# XRONOS_CLOCK_V2_1.net
KiCad netlist of a schematic drawn in EAGLE
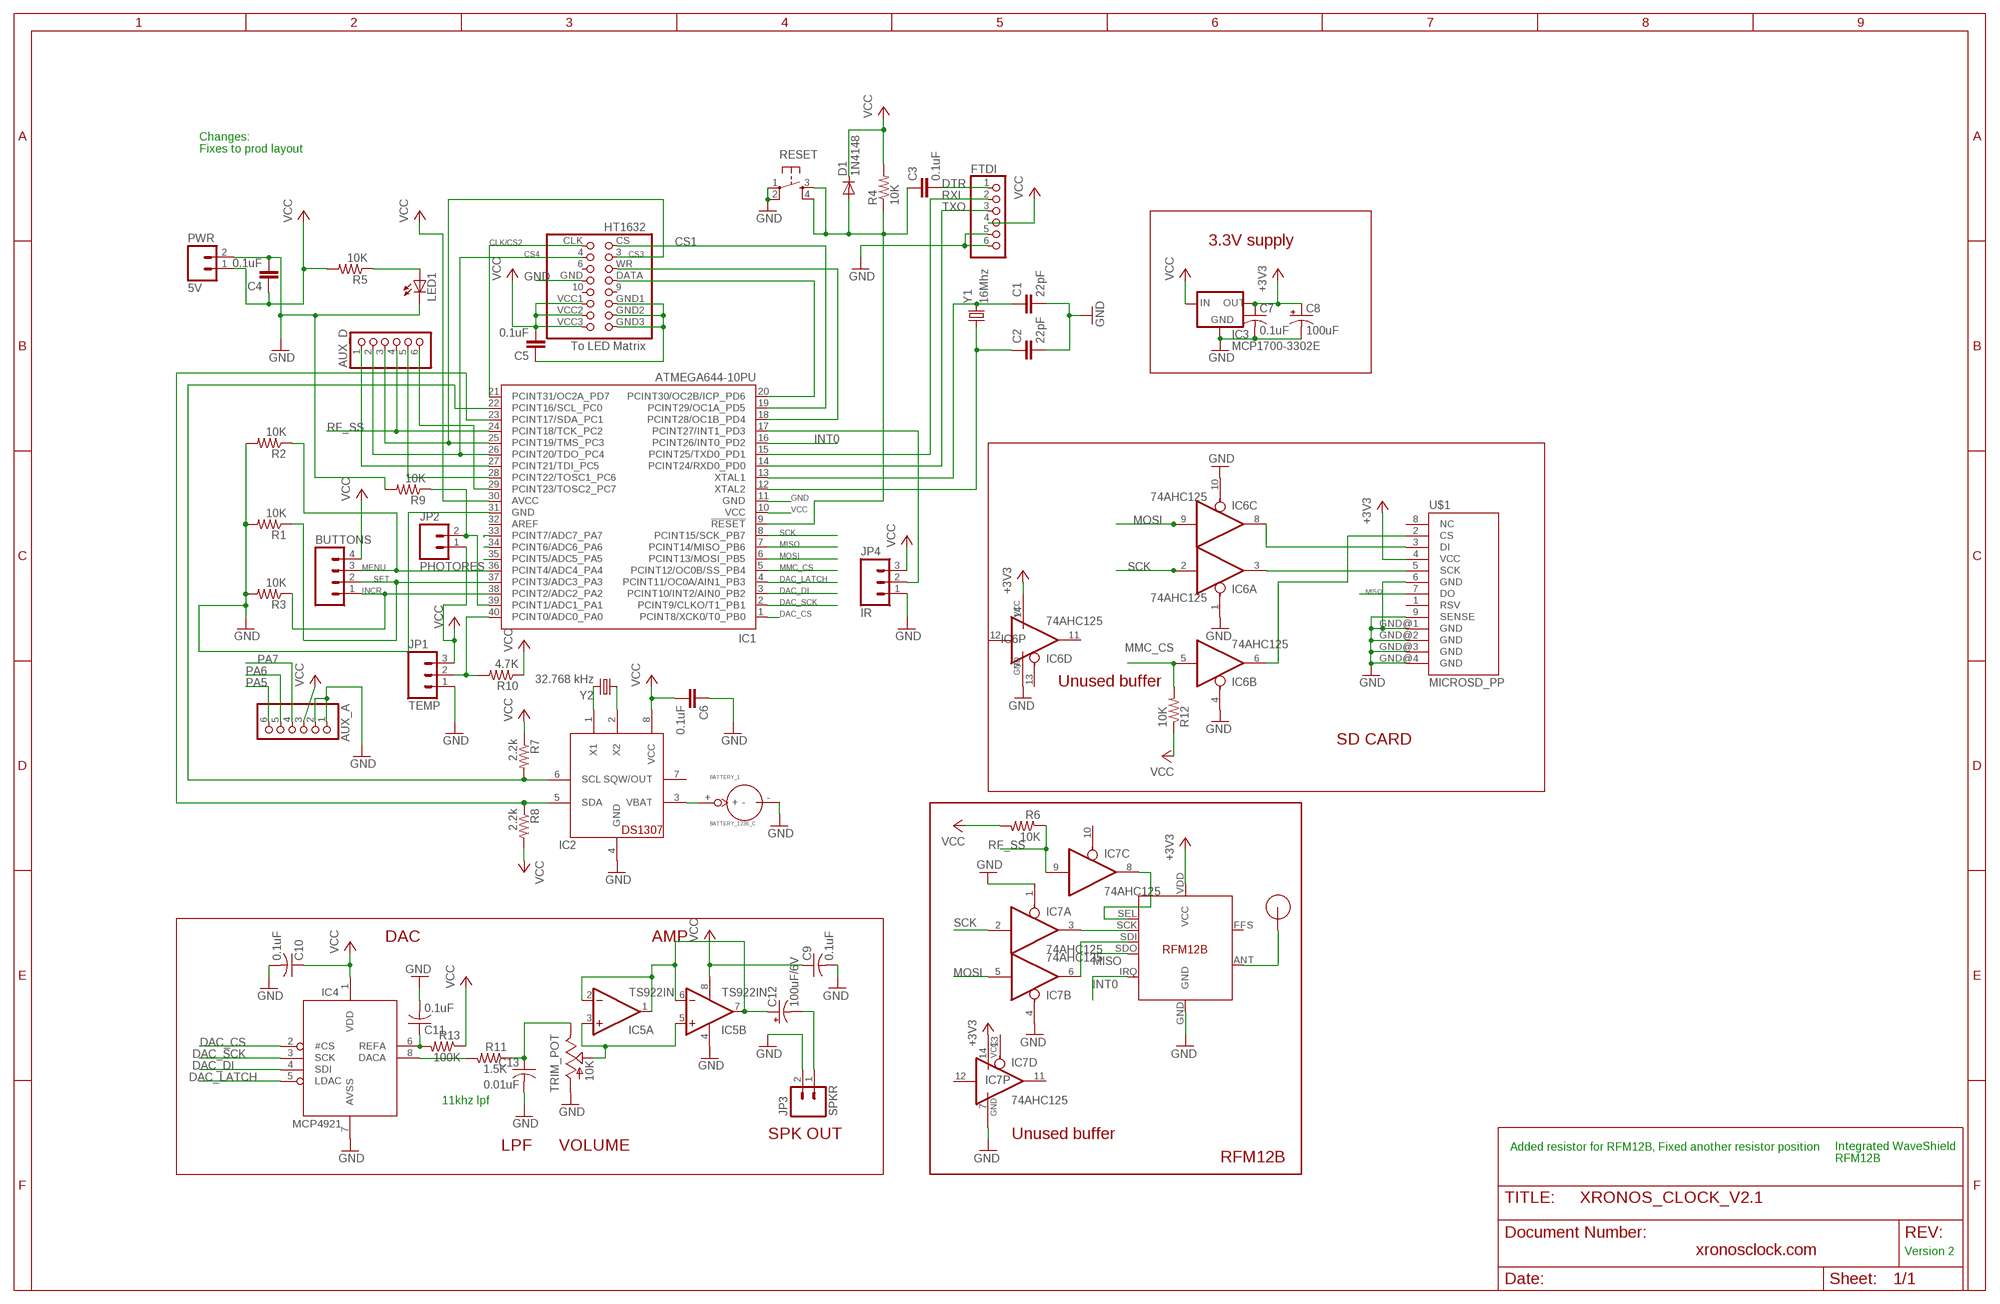
[diagram p0: schematic, sheet 1]

(export (version "E")
  (design (tool "Eeschema 10.0.6"))
  (components
    (comp (ref "AUX_A")
      (value "PINHD-1X6")
      (footprint "eagle-import:1X06")
      (libsource (lib "eagle-import") (part "PINHD-1X6"))
    )
    (comp (ref "AUX_D")
      (value "PINHD-1X6")
      (footprint "eagle-import:1X06")
      (libsource (lib "eagle-import") (part "PINHD-1X6"))
    )
    (comp (ref "BATTERY_1")
      (value "BATTERY_1236_C")
      (footprint "eagle-import:BATTERY_1236_C")
      (libsource (lib "eagle-import") (part "BATTERY_1236_C"))
    )
    (comp (ref "BUTTONS")
      (value "M04POLAR")
      (footprint "eagle-import:MOLEX-1X4")
      (libsource (lib "eagle-import") (part "M04POLAR"))
    )
    (comp (ref "C1")
      (value "22pF")
      (footprint "eagle-import:C025-024X044")
      (libsource (lib "eagle-import") (part "C-EU025-024X044"))
    )
    (comp (ref "C2")
      (value "22pF")
      (footprint "eagle-import:C025-024X044")
      (libsource (lib "eagle-import") (part "C-EU025-024X044"))
    )
    (comp (ref "C3")
      (value "0.1uF")
      (footprint "eagle-import:C025-024X044")
      (libsource (lib "eagle-import") (part "C-EU025-024X044"))
    )
    (comp (ref "C4")
      (value "0.1uF")
      (footprint "eagle-import:C025-024X044")
      (libsource (lib "eagle-import") (part "C-EU025-024X044"))
    )
    (comp (ref "C5")
      (value "0.1uF")
      (footprint "eagle-import:C025-024X044")
      (libsource (lib "eagle-import") (part "C-EU025-024X044"))
    )
    (comp (ref "C6")
      (value "0.1uF")
      (footprint "eagle-import:C025-024X044")
      (libsource (lib "eagle-import") (part "C-EU025-024X044"))
    )
    (comp (ref "C7")
      (value "0.1uF")
      (footprint "eagle-import:C025-025X050")
      (libsource (lib "eagle-import") (part "C-US025-025X050"))
    )
    (comp (ref "C8")
      (value "100uF")
      (footprint "eagle-import:E2,5-5")
      (libsource (lib "eagle-import") (part "CPOL-USE2.5-5"))
    )
    (comp (ref "C9")
      (value "0.1uF")
      (footprint "eagle-import:C025-025X050")
      (libsource (lib "eagle-import") (part "C-US025-025X050"))
    )
    (comp (ref "C10")
      (value "0.1uF")
      (footprint "eagle-import:C025-025X050")
      (libsource (lib "eagle-import") (part "C-US025-025X050"))
    )
    (comp (ref "C11")
      (value "0.1uF")
      (footprint "eagle-import:C025-025X050")
      (libsource (lib "eagle-import") (part "C-US025-025X050"))
    )
    (comp (ref "C12")
      (value "100uF/6V")
      (footprint "eagle-import:E2,5-5")
      (libsource (lib "eagle-import") (part "CPOL-USE2.5-5"))
    )
    (comp (ref "C13")
      (value "0.01uF")
      (footprint "eagle-import:C025-025X050")
      (libsource (lib "eagle-import") (part "C-US025-025X050"))
    )
    (comp (ref "D1")
      (value "1N4148")
      (footprint "eagle-import:DO35-7")
      (libsource (lib "eagle-import") (part "1N4148DO35-7"))
    )
    (comp (ref "FTDI")
      (value "PINHD-1X6")
      (footprint "eagle-import:1X06")
      (libsource (lib "eagle-import") (part "PINHD-1X6"))
    )
    (comp (ref "HT1632")
      (value "To LED Matrix")
      (footprint "eagle-import:IDC2X08")
      (libsource (lib "eagle-import") (part "HT1632"))
    )
    (comp (ref "IC1")
      (value "ATMEGA644-10PU")
      (footprint "eagle-import:DIL40")
      (fields (field (name "MPN") "ATMEGA644V-10PU"))
      (libsource (lib "eagle-import") (part "ATMEGA644-PU10"))
    )
    (comp (ref "IC2")
      (value "DS1307")
      (footprint "eagle-import:DIL08")
      (libsource (lib "eagle-import") (part "DS1307"))
    )
    (comp (ref "IC3")
      (value "MCP1700-3302E")
      (footprint "eagle-import:TO92")
      (libsource (lib "eagle-import") (part "MCP1700TRI"))
    )
    (comp (ref "IC4")
      (value "MCP4921")
      (footprint "eagle-import:DIL08")
      (libsource (lib "eagle-import") (part "MCP4921"))
    )
    (comp (ref "IC5")
      (value "TS922IN")
      (footprint "eagle-import:DIL08")
      (libsource (lib "eagle-import") (part "TL072P"))
    )
    (comp (ref "IC6")
      (value "74AHC125")
      (footprint "eagle-import:DIL14-LARDO")
      (libsource (lib "eagle-import") (part "74125N-LARDO"))
    )
    (comp (ref "IC7")
      (value "74AHC125")
      (footprint "eagle-import:DIL14")
      (libsource (lib "eagle-import") (part "74125N"))
    )
    (comp (ref "JP1")
      (value "TEMP")
      (footprint "eagle-import:MOLEX-1X3")
      (libsource (lib "eagle-import") (part "M03POLAR"))
    )
    (comp (ref "JP2")
      (value "PHOTORES")
      (footprint "eagle-import:MOLEX-1X2")
      (libsource (lib "eagle-import") (part "M02POLAR"))
    )
    (comp (ref "JP3")
      (value "SPKR")
      (footprint "eagle-import:MOLEX-1X2")
      (libsource (lib "eagle-import") (part "M02POLAR"))
    )
    (comp (ref "JP4")
      (value "IR")
      (footprint "eagle-import:MOLEX-1X3_LOCK")
      (libsource (lib "eagle-import") (part "M03POLAR_LOCK"))
    )
    (comp (ref "LED1")
      (value "LED-3MM-NO_SILK")
      (footprint "eagle-import:LED3MM-NS")
      (libsource (lib "eagle-import") (part "LED-3MM-NO_SILK"))
    )
    (comp (ref "PWR")
      (value "5V")
      (footprint "eagle-import:MOLEX-1X2")
      (libsource (lib "eagle-import") (part "M02POLAR"))
    )
    (comp (ref "R1")
      (value "10K")
      (footprint "eagle-import:AXIAL-0.3EZ")
      (libsource (lib "eagle-import") (part "RESISTOREZ"))
    )
    (comp (ref "R2")
      (value "10K")
      (footprint "eagle-import:AXIAL-0.3EZ")
      (libsource (lib "eagle-import") (part "RESISTOREZ"))
    )
    (comp (ref "R3")
      (value "10K")
      (footprint "eagle-import:AXIAL-0.3EZ")
      (libsource (lib "eagle-import") (part "RESISTOREZ"))
    )
    (comp (ref "R4")
      (value "10K")
      (footprint "eagle-import:AXIAL-0.3EZ")
      (libsource (lib "eagle-import") (part "RESISTOREZ"))
    )
    (comp (ref "R5")
      (value "10K")
      (footprint "eagle-import:AXIAL-0.3EZ")
      (libsource (lib "eagle-import") (part "RESISTOREZ"))
    )
    (comp (ref "R6")
      (value "10K")
      (footprint "eagle-import:AXIAL-0.3")
      (libsource (lib "eagle-import") (part "RESISTORAXIAL-0.3"))
    )
    (comp (ref "R7")
      (value "2.2k")
      (footprint "eagle-import:AXIAL-0.3EZ")
      (libsource (lib "eagle-import") (part "RESISTOREZ"))
    )
    (comp (ref "R8")
      (value "2.2k")
      (footprint "eagle-import:AXIAL-0.3EZ")
      (libsource (lib "eagle-import") (part "RESISTOREZ"))
    )
    (comp (ref "R9")
      (value "10K")
      (footprint "eagle-import:AXIAL-0.3EZ")
      (libsource (lib "eagle-import") (part "RESISTOREZ"))
    )
    (comp (ref "R10")
      (value "4.7K")
      (footprint "eagle-import:AXIAL-0.3EZ")
      (libsource (lib "eagle-import") (part "RESISTOREZ"))
    )
    (comp (ref "R11")
      (value "1.5K")
      (footprint "eagle-import:AXIAL-0.3")
      (libsource (lib "eagle-import") (part "RESISTORAXIAL-0.3"))
    )
    (comp (ref "R12")
      (value "10K")
      (footprint "eagle-import:AXIAL-0.3")
      (libsource (lib "eagle-import") (part "RESISTORAXIAL-0.3"))
    )
    (comp (ref "R13")
      (value "100K")
      (footprint "eagle-import:AXIAL-0.3")
      (libsource (lib "eagle-import") (part "RESISTORAXIAL-0.3"))
    )
    (comp (ref "RESET")
      (value "TAC_SWITCHPTH")
      (footprint "eagle-import:TACTILE-PTH")
      (libsource (lib "eagle-import") (part "TAC_SWITCHPTH"))
    )
    (comp (ref "TRIM_POT")
      (value "10K")
      (footprint "eagle-import:B25P")
      (libsource (lib "eagle-import") (part "TRIM_US-B25P"))
    )
    (comp (ref "U$1")
      (value "MICROSD_PP")
      (footprint "eagle-import:MICROSD_PP")
      (libsource (lib "eagle-import") (part "MICROSD_PP"))
    )
    (comp (ref "U$2")
      (value "RFM12B")
      (footprint "eagle-import:RFM12B")
      (libsource (lib "eagle-import") (part "RFM12B"))
    )
    (comp (ref "U$3")
      (value "RFM12B_ANTENNA")
      (footprint "eagle-import:RFM12B-ANTENNA")
      (libsource (lib "eagle-import") (part "RFM12B_ANTENNA"))
    )
    (comp (ref "Y1")
      (value "16Mhz")
      (footprint "eagle-import:HC49US")
      (libsource (lib "eagle-import") (part "CRYSTALHC49US"))
    )
    (comp (ref "Y2")
      (value "32.768 kHz")
      (footprint "eagle-import:TC26HEZ")
      (libsource (lib "eagle-import") (part "CRYSTALTC26H_EZ"))
    )
  )
  (nets
    (net (code "1") (name "+3V3") (class "Default")
      (node (ref "C7") (pin "1") (pinfunction "1_1") (pintype "passive"))
      (node (ref "C8") (pin "+") (pinfunction "+_+") (pintype "passive"))
      (node (ref "IC3") (pin "3") (pinfunction "OUT_3") (pintype "passive"))
      (node (ref "IC6") (pin "14") (pinfunction "VCC_14") (pintype "power_in"))
      (node (ref "IC7") (pin "14") (pinfunction "VCC_14") (pintype "power_in"))
      (node (ref "U$1") (pin "4") (pinfunction "VCC_4") (pintype "bidirectional"))
      (node (ref "U$2") (pin "VDD") (pinfunction "VCC_VDD") (pintype "power_in"))
    )
    (net (code "2") (name "/CLK{slash}CS2") (class "Default")
      (node (ref "HT1632") (pin "CLK") (pinfunction "2_CLK") (pintype "passive"))
      (node (ref "IC1") (pin "21") (pinfunction "PCINT31/OC2A_PD7_21") (pintype "bidirectional"))
    )
    (net (code "3") (name "/CS1") (class "Default")
      (node (ref "HT1632") (pin "CS") (pinfunction "1_CS") (pintype "passive"))
      (node (ref "IC1") (pin "19") (pinfunction "PCINT29/OC1A_PD5_19") (pintype "bidirectional"))
    )
    (net (code "4") (name "/CS3") (class "Default")
      (node (ref "AUX_D") (pin "3") (pinfunction "3_3") (pintype "passive"))
      (node (ref "HT1632") (pin "3") (pinfunction "3_3") (pintype "passive"))
      (node (ref "IC1") (pin "25") (pinfunction "PCINT19/TMS_PC3_25") (pintype "bidirectional"))
    )
    (net (code "5") (name "/CS4") (class "Default")
      (node (ref "AUX_D") (pin "2") (pinfunction "2_2") (pintype "passive"))
      (node (ref "HT1632") (pin "4") (pinfunction "4_4") (pintype "passive"))
      (node (ref "IC1") (pin "26") (pinfunction "PCINT20/TDO_PC4_26") (pintype "bidirectional"))
    )
    (net (code "6") (name "/DAC_CS") (class "Default")
      (node (ref "IC1") (pin "1") (pinfunction "PCINT8/XCK0/T0_PB0_1") (pintype "bidirectional"))
      (node (ref "IC4") (pin "2") (pinfunction "#CS_2") (pintype "input"))
    )
    (net (code "7") (name "/DAC_DI") (class "Default")
      (node (ref "IC1") (pin "3") (pinfunction "PCINT10/INT2/AIN0_PB2_3") (pintype "bidirectional"))
      (node (ref "IC4") (pin "4") (pinfunction "SDI_4") (pintype "input"))
    )
    (net (code "8") (name "/DAC_LATCH") (class "Default")
      (node (ref "IC1") (pin "4") (pinfunction "PCINT11/OC0A/AIN1_PB3_4") (pintype "bidirectional"))
      (node (ref "IC4") (pin "5") (pinfunction "LDAC_5") (pintype "input"))
    )
    (net (code "9") (name "/DAC_SCK") (class "Default")
      (node (ref "IC1") (pin "2") (pinfunction "PCINT9/CLKO/T1_PB1_2") (pintype "bidirectional"))
      (node (ref "IC4") (pin "3") (pinfunction "SCK_3") (pintype "input"))
    )
    (net (code "10") (name "/DTR") (class "Default")
      (node (ref "C3") (pin "2") (pinfunction "2_2") (pintype "passive"))
      (node (ref "FTDI") (pin "1") (pinfunction "1_1") (pintype "passive"))
    )
    (net (code "11") (name "/INCR") (class "Default")
      (node (ref "BUTTONS") (pin "1") (pinfunction "1_1") (pintype "passive"))
      (node (ref "IC1") (pin "38") (pinfunction "PCINT2/ADC2_PA2_38") (pintype "bidirectional"))
      (node (ref "R3") (pin "P$1") (pinfunction "1_P$1") (pintype "passive"))
    )
    (net (code "12") (name "/INT0") (class "Default")
      (node (ref "IC1") (pin "16") (pinfunction "PCINT26/INT0_PD2_16") (pintype "bidirectional"))
      (node (ref "U$2") (pin "IRQ") (pinfunction "IRQ_IRQ") (pintype "open_collector"))
    )
    (net (code "13") (name "/MENU") (class "Default")
      (node (ref "BUTTONS") (pin "3") (pinfunction "3_3") (pintype "passive"))
      (node (ref "IC1") (pin "36") (pinfunction "PCINT4/ADC4_PA4_36") (pintype "bidirectional"))
      (node (ref "R2") (pin "P$1") (pinfunction "1_P$1") (pintype "passive"))
    )
    (net (code "14") (name "/MISO") (class "Default")
      (node (ref "IC1") (pin "7") (pinfunction "PCINT14/MISO_PB6_7") (pintype "bidirectional"))
      (node (ref "U$1") (pin "7") (pinfunction "DO_7") (pintype "bidirectional"))
      (node (ref "U$2") (pin "SDO") (pinfunction "SDO_SDO") (pintype "output"))
    )
    (net (code "15") (name "/MMC_CS") (class "Default")
      (node (ref "IC1") (pin "5") (pinfunction "PCINT12/OC0B/SS_PB4_5") (pintype "bidirectional"))
      (node (ref "IC6") (pin "5") (pinfunction "I_5") (pintype "input"))
      (node (ref "R12") (pin "P$2") (pinfunction "2_P$2") (pintype "passive"))
    )
    (net (code "16") (name "/MOSI") (class "Default")
      (node (ref "IC1") (pin "6") (pinfunction "PCINT13/MOSI_PB5_6") (pintype "bidirectional"))
      (node (ref "IC6") (pin "9") (pinfunction "I_9") (pintype "input"))
      (node (ref "IC7") (pin "5") (pinfunction "I_5") (pintype "input"))
    )
    (net (code "17") (name "/PA5") (class "Default")
      (node (ref "AUX_A") (pin "6") (pinfunction "6_6") (pintype "passive"))
      (node (ref "IC1") (pin "35") (pinfunction "PCINT5/ADC5_PA5_35") (pintype "bidirectional"))
    )
    (net (code "18") (name "/PA6") (class "Default")
      (node (ref "AUX_A") (pin "5") (pinfunction "5_5") (pintype "passive"))
      (node (ref "IC1") (pin "34") (pinfunction "PCINT6/ADC6_PA6_34") (pintype "bidirectional"))
    )
    (net (code "19") (name "/PA7") (class "Default")
      (node (ref "AUX_A") (pin "4") (pinfunction "4_4") (pintype "passive"))
      (node (ref "IC1") (pin "33") (pinfunction "PCINT7/ADC7_PA7_33") (pintype "bidirectional"))
    )
    (net (code "20") (name "/RF_SS") (class "Default")
      (node (ref "AUX_D") (pin "4") (pinfunction "4_4") (pintype "passive"))
      (node (ref "IC1") (pin "24") (pinfunction "PCINT18/TCK_PC2_24") (pintype "bidirectional"))
      (node (ref "IC7") (pin "9") (pinfunction "I_9") (pintype "input"))
      (node (ref "R6") (pin "P$1") (pinfunction "1_P$1") (pintype "passive"))
    )
    (net (code "21") (name "/RXI") (class "Default")
      (node (ref "FTDI") (pin "2") (pinfunction "2_2") (pintype "passive"))
      (node (ref "IC1") (pin "15") (pinfunction "PCINT25/TXD0_PD1_15") (pintype "bidirectional"))
    )
    (net (code "22") (name "/SCK") (class "Default")
      (node (ref "IC1") (pin "8") (pinfunction "PCINT15/SCK_PB7_8") (pintype "bidirectional"))
      (node (ref "IC6") (pin "2") (pinfunction "I_2") (pintype "input"))
      (node (ref "IC7") (pin "2") (pinfunction "I_2") (pintype "input"))
    )
    (net (code "23") (name "/SET") (class "Default")
      (node (ref "BUTTONS") (pin "2") (pinfunction "2_2") (pintype "passive"))
      (node (ref "IC1") (pin "37") (pinfunction "PCINT3/ADC3_PA3_37") (pintype "bidirectional"))
      (node (ref "R1") (pin "P$1") (pinfunction "1_P$1") (pintype "passive"))
    )
    (net (code "24") (name "/TXO") (class "Default")
      (node (ref "FTDI") (pin "3") (pinfunction "3_3") (pintype "passive"))
      (node (ref "IC1") (pin "14") (pinfunction "PCINT24/RXD0_PD0_14") (pintype "bidirectional"))
    )
    (net (code "25") (name "GND") (class "Default")
      (node (ref "AUX_A") (pin "1") (pinfunction "1_1") (pintype "passive"))
      (node (ref "AUX_A") (pin "2") (pinfunction "2_2") (pintype "passive"))
      (node (ref "BATTERY_1") (pin "-") (pinfunction "-_-") (pintype "bidirectional"))
      (node (ref "C1") (pin "2") (pinfunction "2_2") (pintype "passive"))
      (node (ref "C10") (pin "2") (pinfunction "2_2") (pintype "passive"))
      (node (ref "C11") (pin "2") (pinfunction "2_2") (pintype "passive"))
      (node (ref "C13") (pin "2") (pinfunction "2_2") (pintype "passive"))
      (node (ref "C2") (pin "2") (pinfunction "2_2") (pintype "passive"))
      (node (ref "C4") (pin "2") (pinfunction "2_2") (pintype "passive"))
      (node (ref "C6") (pin "1") (pinfunction "1_1") (pintype "passive"))
      (node (ref "C7") (pin "2") (pinfunction "2_2") (pintype "passive"))
      (node (ref "C8") (pin "-") (pinfunction "-_-") (pintype "passive"))
      (node (ref "C9") (pin "2") (pinfunction "2_2") (pintype "passive"))
      (node (ref "FTDI") (pin "5") (pinfunction "5_5") (pintype "passive"))
      (node (ref "FTDI") (pin "6") (pinfunction "6_6") (pintype "passive"))
      (node (ref "HT1632") (pin "GND") (pinfunction "8_GND") (pintype "passive"))
      (node (ref "IC1") (pin "11") (pinfunction "GND_11") (pintype "power_in"))
      (node (ref "IC1") (pin "31") (pinfunction "GND_31") (pintype "power_in"))
      (node (ref "IC2") (pin "4") (pinfunction "GND_4") (pintype "power_in"))
      (node (ref "IC3") (pin "1") (pinfunction "GND_1") (pintype "input"))
      (node (ref "IC4") (pin "7") (pinfunction "AVSS_7") (pintype "power_in"))
      (node (ref "IC5") (pin "4") (pinfunction "V-_4") (pintype "power_in"))
      (node (ref "IC6") (pin "1") (pinfunction "OE_1") (pintype "input"))
      (node (ref "IC6") (pin "10") (pinfunction "OE_10") (pintype "input"))
      (node (ref "IC6") (pin "4") (pinfunction "OE_4") (pintype "input"))
      (node (ref "IC6") (pin "7") (pinfunction "GND_7") (pintype "power_in"))
      (node (ref "IC7") (pin "1") (pinfunction "OE_1") (pintype "input"))
      (node (ref "IC7") (pin "4") (pinfunction "OE_4") (pintype "input"))
      (node (ref "IC7") (pin "7") (pinfunction "GND_7") (pintype "power_in"))
      (node (ref "JP1") (pin "1") (pinfunction "1_1") (pintype "passive"))
      (node (ref "JP3") (pin "2") (pinfunction "2_2") (pintype "passive"))
      (node (ref "JP4") (pin "1") (pinfunction "1_1") (pintype "passive"))
      (node (ref "LED1") (pin "K") (pinfunction "C_K") (pintype "passive"))
      (node (ref "PWR") (pin "2") (pinfunction "2_2") (pintype "passive"))
      (node (ref "R1") (pin "P$2") (pinfunction "2_P$2") (pintype "passive"))
      (node (ref "R2") (pin "P$2") (pinfunction "2_P$2") (pintype "passive"))
      (node (ref "R3") (pin "P$2") (pinfunction "2_P$2") (pintype "passive"))
      (node (ref "R9") (pin "P$2") (pinfunction "2_P$2") (pintype "passive"))
      (node (ref "RESET") (pin "1") (pinfunction "1_1") (pintype "passive"))
      (node (ref "RESET") (pin "2") (pinfunction "2_2") (pintype "passive"))
      (node (ref "TRIM_POT") (pin "A") (pinfunction "A_A") (pintype "passive"))
      (node (ref "U$1") (pin "6") (pinfunction "GND_6") (pintype "bidirectional"))
      (node (ref "U$1") (pin "9") (pinfunction "SENSE_9") (pintype "bidirectional"))
      (node (ref "U$1") (pin "GND@1") (pinfunction "GND_GND@1") (pintype "bidirectional"))
      (node (ref "U$1") (pin "GND@2") (pinfunction "GND_GND@2") (pintype "bidirectional"))
      (node (ref "U$1") (pin "GND@3") (pinfunction "GND_GND@3") (pintype "bidirectional"))
      (node (ref "U$1") (pin "GND@4") (pinfunction "GND_GND@4") (pintype "bidirectional"))
      (node (ref "U$2") (pin "GND") (pinfunction "GND_GND") (pintype "power_in"))
    )
    (net (code "26") (name "Net-(C12-Pad-)") (class "Default")
      (node (ref "C12") (pin "-") (pinfunction "-_-") (pintype "passive"))
      (node (ref "JP3") (pin "1") (pinfunction "1_1") (pintype "passive"))
    )
    (net (code "27") (name "Net-(HT1632-5)") (class "Default")
      (node (ref "HT1632") (pin "WR") (pinfunction "5_WR") (pintype "passive"))
      (node (ref "IC1") (pin "18") (pinfunction "PCINT28/OC1B_PD4_18") (pintype "bidirectional"))
    )
    (net (code "28") (name "Net-(HT1632-7)") (class "Default")
      (node (ref "HT1632") (pin "DATA") (pinfunction "7_DATA") (pintype "passive"))
      (node (ref "IC1") (pin "20") (pinfunction "PCINT30/OC2B/ICP_PD6_20") (pintype "bidirectional"))
    )
    (net (code "29") (name "Net-(HT1632-11)") (class "Default")
      (node (ref "C5") (pin "1") (pinfunction "1_1") (pintype "passive"))
      (node (ref "HT1632") (pin "GND1") (pinfunction "11_GND1") (pintype "passive"))
      (node (ref "HT1632") (pin "GND2") (pinfunction "13_GND2") (pintype "passive"))
      (node (ref "HT1632") (pin "GND3") (pinfunction "15_GND3") (pintype "passive"))
    )
    (net (code "30") (name "Net-(IC1-PCINT0{slash}ADC0_PA0)") (class "Default")
      (node (ref "IC1") (pin "40") (pinfunction "PCINT0/ADC0_PA0_40") (pintype "bidirectional"))
      (node (ref "JP1") (pin "2") (pinfunction "2_2") (pintype "passive"))
      (node (ref "R10") (pin "P$2") (pinfunction "2_P$2") (pintype "passive"))
    )
    (net (code "31") (name "Net-(IC1-PCINT1{slash}ADC1_PA1)") (class "Default")
      (node (ref "IC1") (pin "39") (pinfunction "PCINT1/ADC1_PA1_39") (pintype "bidirectional"))
      (node (ref "JP2") (pin "2") (pinfunction "2_2") (pintype "passive"))
      (node (ref "R9") (pin "P$1") (pinfunction "1_P$1") (pintype "passive"))
    )
    (net (code "32") (name "Net-(IC1-PCINT16{slash}SCL_PC0)") (class "Default")
      (node (ref "IC1") (pin "22") (pinfunction "PCINT16/SCL_PC0_22") (pintype "bidirectional"))
      (node (ref "IC2") (pin "6") (pinfunction "SCL_6") (pintype "bidirectional"))
      (node (ref "R7") (pin "P$2") (pinfunction "2_P$2") (pintype "passive"))
    )
    (net (code "33") (name "Net-(IC1-PCINT17{slash}SDA_PC1)") (class "Default")
      (node (ref "IC1") (pin "23") (pinfunction "PCINT17/SDA_PC1_23") (pintype "bidirectional"))
      (node (ref "IC2") (pin "5") (pinfunction "SDA_5") (pintype "bidirectional"))
      (node (ref "R8") (pin "P$1") (pinfunction "1_P$1") (pintype "passive"))
    )
    (net (code "34") (name "Net-(IC1-PCINT21{slash}TDI_PC5)") (class "Default")
      (node (ref "AUX_D") (pin "1") (pinfunction "1_1") (pintype "passive"))
      (node (ref "IC1") (pin "27") (pinfunction "PCINT21/TDI_PC5_27") (pintype "bidirectional"))
    )
    (net (code "35") (name "Net-(IC1-PCINT22{slash}TOSC1_PC6)") (class "Default")
      (node (ref "AUX_D") (pin "5") (pinfunction "5_5") (pintype "passive"))
      (node (ref "IC1") (pin "28") (pinfunction "PCINT22/TOSC1_PC6_28") (pintype "bidirectional"))
    )
    (net (code "36") (name "Net-(IC1-PCINT23{slash}TOSC2_PC7)") (class "Default")
      (node (ref "AUX_D") (pin "6") (pinfunction "6_6") (pintype "passive"))
      (node (ref "IC1") (pin "29") (pinfunction "PCINT23/TOSC2_PC7_29") (pintype "bidirectional"))
    )
    (net (code "37") (name "Net-(IC1-PCINT27{slash}INT1_PD3)") (class "Default")
      (node (ref "IC1") (pin "17") (pinfunction "PCINT27/INT1_PD3_17") (pintype "bidirectional"))
      (node (ref "JP4") (pin "2") (pinfunction "2_2") (pintype "passive"))
    )
    (net (code "38") (name "Net-(IC1-XTAL1)") (class "Default")
      (node (ref "C1") (pin "1") (pinfunction "1_1") (pintype "passive"))
      (node (ref "IC1") (pin "13") (pinfunction "XTAL1_13") (pintype "input"))
      (node (ref "Y1") (pin "2") (pinfunction "2_2") (pintype "passive"))
    )
    (net (code "39") (name "Net-(IC1-XTAL2)") (class "Default")
      (node (ref "C2") (pin "1") (pinfunction "1_1") (pintype "passive"))
      (node (ref "IC1") (pin "12") (pinfunction "XTAL2_12") (pintype "output"))
      (node (ref "Y1") (pin "1") (pinfunction "1_1") (pintype "passive"))
    )
    (net (code "40") (name "Net-(IC1-~{RESET})") (class "Default")
      (node (ref "C3") (pin "1") (pinfunction "1_1") (pintype "passive"))
      (node (ref "D1") (pin "A") (pinfunction "A_A") (pintype "passive"))
      (node (ref "IC1") (pin "9") (pinfunction "~{RESET}_9") (pintype "input"))
      (node (ref "R4") (pin "P$1") (pinfunction "1_P$1") (pintype "passive"))
      (node (ref "RESET") (pin "3") (pinfunction "3_3") (pintype "passive"))
      (node (ref "RESET") (pin "4") (pinfunction "4_4") (pintype "passive"))
    )
    (net (code "41") (name "Net-(IC2-VBAT)") (class "Default")
      (node (ref "BATTERY_1") (pin "+") (pinfunction "+_+") (pintype "bidirectional"))
      (node (ref "IC2") (pin "3") (pinfunction "VBAT_3") (pintype "power_in"))
    )
    (net (code "42") (name "Net-(IC2-X1)") (class "Default")
      (node (ref "IC2") (pin "1") (pinfunction "X1_1") (pintype "passive"))
      (node (ref "Y2") (pin "2") (pinfunction "2_2") (pintype "passive"))
    )
    (net (code "43") (name "Net-(IC2-X2)") (class "Default")
      (node (ref "IC2") (pin "2") (pinfunction "X2_2") (pintype "passive"))
      (node (ref "Y2") (pin "1") (pinfunction "1_1") (pintype "passive"))
    )
    (net (code "44") (name "Net-(IC4-DACA)") (class "Default")
      (node (ref "IC4") (pin "8") (pinfunction "DACA_8") (pintype "output"))
      (node (ref "R11") (pin "P$2") (pinfunction "2_P$2") (pintype "passive"))
    )
    (net (code "45") (name "Net-(IC4-REFA)") (class "Default")
      (node (ref "C11") (pin "1") (pinfunction "1_1") (pintype "passive"))
      (node (ref "IC4") (pin "6") (pinfunction "REFA_6") (pintype "input"))
      (node (ref "R13") (pin "P$2") (pinfunction "2_P$2") (pintype "passive"))
    )
    (net (code "46") (name "Net-(IC5A-+IN)") (class "Default")
      (node (ref "IC5") (pin "3") (pinfunction "+IN_3") (pintype "input"))
      (node (ref "IC5") (pin "5") (pinfunction "+IN_5") (pintype "input"))
      (node (ref "TRIM_POT") (pin "S") (pinfunction "S_S") (pintype "passive"))
    )
    (net (code "47") (name "Net-(IC5A--IN)") (class "Default")
      (node (ref "C12") (pin "+") (pinfunction "+_+") (pintype "passive"))
      (node (ref "IC5") (pin "1") (pinfunction "OUT_1") (pintype "output"))
      (node (ref "IC5") (pin "2") (pinfunction "-IN_2") (pintype "input"))
      (node (ref "IC5") (pin "6") (pinfunction "-IN_6") (pintype "input"))
      (node (ref "IC5") (pin "7") (pinfunction "OUT_7") (pintype "output"))
    )
    (net (code "48") (name "Net-(IC6A-O)") (class "Default")
      (node (ref "IC6") (pin "3") (pinfunction "O_3") (pintype "tri_state"))
      (node (ref "U$1") (pin "5") (pinfunction "SCK_5") (pintype "bidirectional"))
    )
    (net (code "49") (name "Net-(IC6B-O)") (class "Default")
      (node (ref "IC6") (pin "6") (pinfunction "O_6") (pintype "tri_state"))
      (node (ref "U$1") (pin "2") (pinfunction "CS_2") (pintype "bidirectional"))
    )
    (net (code "50") (name "Net-(IC6C-O)") (class "Default")
      (node (ref "IC6") (pin "8") (pinfunction "O_8") (pintype "tri_state"))
      (node (ref "U$1") (pin "3") (pinfunction "DI_3") (pintype "bidirectional"))
    )
    (net (code "51") (name "Net-(IC7A-O)") (class "Default")
      (node (ref "IC7") (pin "3") (pinfunction "O_3") (pintype "tri_state"))
      (node (ref "U$2") (pin "SCK") (pinfunction "SCK_SCK") (pintype "input"))
    )
    (net (code "52") (name "Net-(IC7B-O)") (class "Default")
      (node (ref "IC7") (pin "6") (pinfunction "O_6") (pintype "tri_state"))
      (node (ref "U$2") (pin "SDI") (pinfunction "SDI_SDI") (pintype "input"))
    )
    (net (code "53") (name "Net-(IC7C-O)") (class "Default")
      (node (ref "IC7") (pin "8") (pinfunction "O_8") (pintype "tri_state"))
      (node (ref "U$2") (pin "SEL") (pinfunction "SEL_SEL") (pintype "input"))
    )
    (net (code "54") (name "Net-(R5-1)") (class "Default")
      (node (ref "LED1") (pin "A") (pinfunction "A_A") (pintype "passive"))
      (node (ref "R5") (pin "P$1") (pinfunction "1_P$1") (pintype "passive"))
    )
    (net (code "55") (name "Net-(R11-1)") (class "Default")
      (node (ref "C13") (pin "1") (pinfunction "1_1") (pintype "passive"))
      (node (ref "R11") (pin "P$1") (pinfunction "1_P$1") (pintype "passive"))
      (node (ref "TRIM_POT") (pin "E") (pinfunction "E_E") (pintype "passive"))
    )
    (net (code "56") (name "Net-(U$3-1)") (class "Default")
      (node (ref "U$2") (pin "ANT") (pinfunction "ANT_ANT") (pintype "passive"))
      (node (ref "U$3") (pin "P$1") (pinfunction "1_P$1") (pintype "bidirectional"))
    )
    (net (code "57") (name "VCC") (class "Default")
      (node (ref "AUX_A") (pin "3") (pinfunction "3_3") (pintype "passive"))
      (node (ref "BUTTONS") (pin "4") (pinfunction "4_4") (pintype "passive"))
      (node (ref "C10") (pin "1") (pinfunction "1_1") (pintype "passive"))
      (node (ref "C4") (pin "1") (pinfunction "1_1") (pintype "passive"))
      (node (ref "C5") (pin "2") (pinfunction "2_2") (pintype "passive"))
      (node (ref "C6") (pin "2") (pinfunction "2_2") (pintype "passive"))
      (node (ref "C9") (pin "1") (pinfunction "1_1") (pintype "passive"))
      (node (ref "D1") (pin "C") (pinfunction "C_C") (pintype "passive"))
      (node (ref "FTDI") (pin "4") (pinfunction "4_4") (pintype "passive"))
      (node (ref "HT1632") (pin "VCC1") (pinfunction "12_VCC1") (pintype "passive"))
      (node (ref "HT1632") (pin "VCC2") (pinfunction "14_VCC2") (pintype "passive"))
      (node (ref "HT1632") (pin "VCC3") (pinfunction "16_VCC3") (pintype "passive"))
      (node (ref "IC1") (pin "10") (pinfunction "VCC_10") (pintype "power_in"))
      (node (ref "IC1") (pin "30") (pinfunction "AVCC_30") (pintype "power_in"))
      (node (ref "IC2") (pin "8") (pinfunction "VCC_8") (pintype "power_in"))
      (node (ref "IC3") (pin "2") (pinfunction "IN_2") (pintype "input"))
      (node (ref "IC4") (pin "1") (pinfunction "VDD_1") (pintype "power_in"))
      (node (ref "IC5") (pin "8") (pinfunction "V+_8") (pintype "power_in"))
      (node (ref "JP1") (pin "3") (pinfunction "3_3") (pintype "passive"))
      (node (ref "JP2") (pin "1") (pinfunction "1_1") (pintype "passive"))
      (node (ref "JP4") (pin "3") (pinfunction "3_3") (pintype "passive"))
      (node (ref "PWR") (pin "1") (pinfunction "1_1") (pintype "passive"))
      (node (ref "R10") (pin "P$1") (pinfunction "1_P$1") (pintype "passive"))
      (node (ref "R12") (pin "P$1") (pinfunction "1_P$1") (pintype "passive"))
      (node (ref "R13") (pin "P$1") (pinfunction "1_P$1") (pintype "passive"))
      (node (ref "R4") (pin "P$2") (pinfunction "2_P$2") (pintype "passive"))
      (node (ref "R5") (pin "P$2") (pinfunction "2_P$2") (pintype "passive"))
      (node (ref "R6") (pin "P$2") (pinfunction "2_P$2") (pintype "passive"))
      (node (ref "R7") (pin "P$1") (pinfunction "1_P$1") (pintype "passive"))
      (node (ref "R8") (pin "P$2") (pinfunction "2_P$2") (pintype "passive"))
    )
    (net (code "58") (name "unconnected-(HT1632-Pad6)") (class "Default")
      (node (ref "HT1632") (pin "6") (pinfunction "6_6") (pintype "passive"))
    )
    (net (code "59") (name "unconnected-(HT1632-Pad9)") (class "Default")
      (node (ref "HT1632") (pin "9") (pinfunction "9_9") (pintype "passive"))
    )
    (net (code "60") (name "unconnected-(HT1632-Pad10)") (class "Default")
      (node (ref "HT1632") (pin "10") (pinfunction "10_10") (pintype "passive"))
    )
    (net (code "61") (name "unconnected-(IC1-AREF-Pad32)") (class "Default")
      (node (ref "IC1") (pin "32") (pinfunction "AREF_32") (pintype "passive"))
    )
    (net (code "62") (name "unconnected-(IC2-SQW{slash}OUT-Pad7)") (class "Default")
      (node (ref "IC2") (pin "7") (pinfunction "SQW/OUT_7") (pintype "bidirectional"))
    )
    (net (code "63") (name "unconnected-(IC6D-I-Pad12)") (class "Default")
      (node (ref "IC6") (pin "12") (pinfunction "I_12") (pintype "input"))
    )
    (net (code "64") (name "unconnected-(IC6D-O-Pad11)") (class "Default")
      (node (ref "IC6") (pin "11") (pinfunction "O_11") (pintype "tri_state"))
    )
    (net (code "65") (name "unconnected-(IC6D-OE-Pad13)") (class "Default")
      (node (ref "IC6") (pin "13") (pinfunction "OE_13") (pintype "input"))
    )
    (net (code "66") (name "unconnected-(IC7C-OE-Pad10)") (class "Default")
      (node (ref "IC7") (pin "10") (pinfunction "OE_10") (pintype "input"))
    )
    (net (code "67") (name "unconnected-(IC7D-I-Pad12)") (class "Default")
      (node (ref "IC7") (pin "12") (pinfunction "I_12") (pintype "input"))
    )
    (net (code "68") (name "unconnected-(IC7D-O-Pad11)") (class "Default")
      (node (ref "IC7") (pin "11") (pinfunction "O_11") (pintype "tri_state"))
    )
    (net (code "69") (name "unconnected-(IC7D-OE-Pad13)") (class "Default")
      (node (ref "IC7") (pin "13") (pinfunction "OE_13") (pintype "input"))
    )
    (net (code "70") (name "unconnected-(U$1-NC-Pad8)") (class "Default")
      (node (ref "U$1") (pin "8") (pinfunction "NC_8") (pintype "bidirectional"))
    )
    (net (code "71") (name "unconnected-(U$1-RSV-Pad1)") (class "Default")
      (node (ref "U$1") (pin "1") (pinfunction "RSV_1") (pintype "bidirectional"))
    )
    (net (code "72") (name "unconnected-(U$2-PadFFS)") (class "Default")
      (node (ref "U$2") (pin "FFS") (pinfunction "FFS_FFS") (pintype "bidirectional"))
    )
  )
)
